# uc4h_esc_kiss_v100.net
KiCad netlist of a schematic drawn in EAGLE
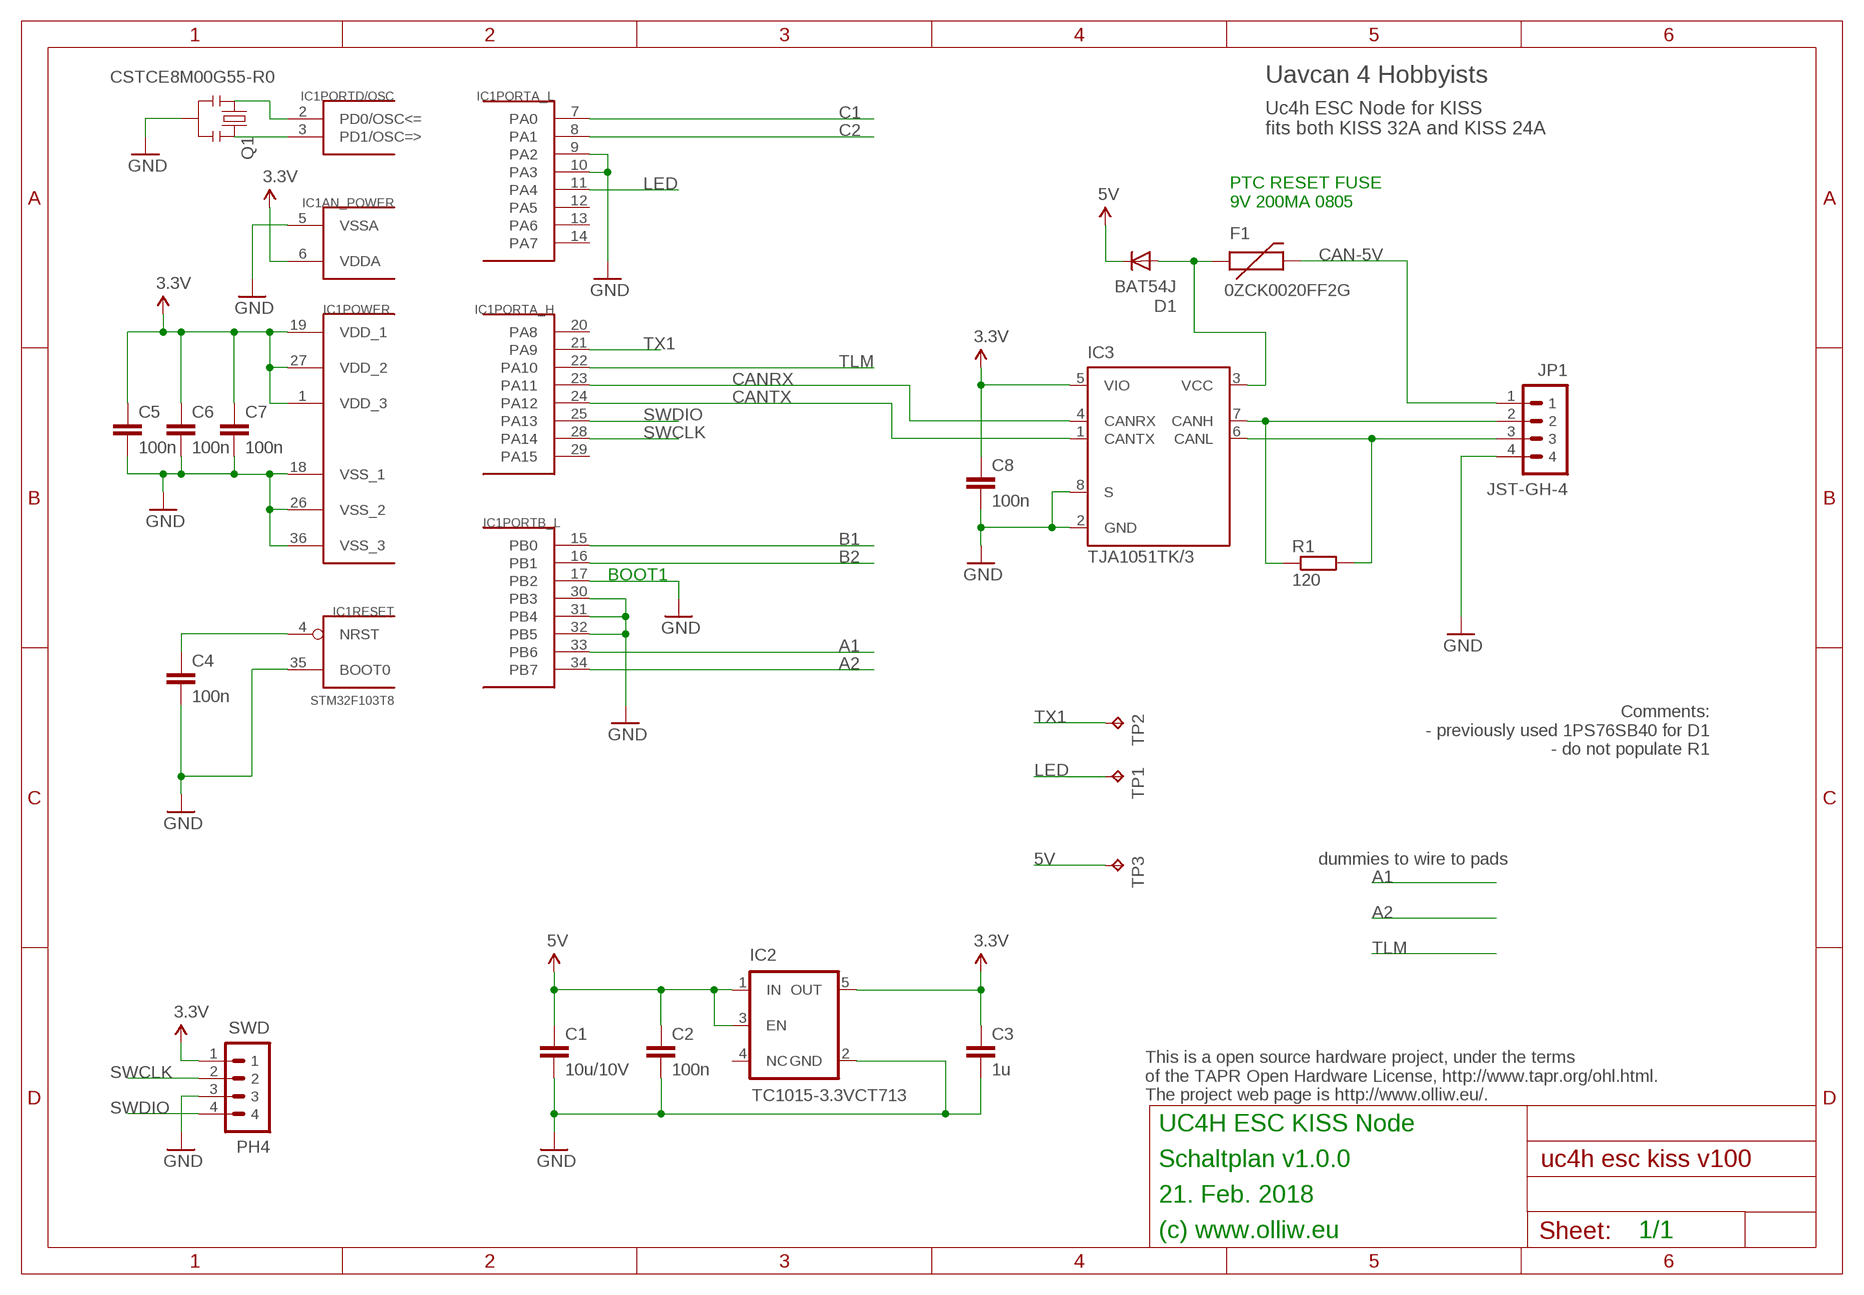
[diagram p0: schematic, sheet 1]

(export (version "E")
  (design (tool "Eeschema 10.0.6"))
  (components
    (comp (ref "C1")
      (value "10u/10V")
      (footprint "eagle-import:C1206")
      (libsource (lib "eagle-import") (part "C-EUC1206"))
    )
    (comp (ref "C2")
      (value "100n")
      (footprint "eagle-import:C0603K")
      (libsource (lib "eagle-import") (part "C-EUC0603K"))
    )
    (comp (ref "C3")
      (value "1u")
      (footprint "eagle-import:C0603K")
      (libsource (lib "eagle-import") (part "C-EUC0603K"))
    )
    (comp (ref "C4")
      (value "100n")
      (footprint "eagle-import:C0603K")
      (libsource (lib "eagle-import") (part "C-EUC0603K"))
    )
    (comp (ref "C5")
      (value "100n")
      (footprint "eagle-import:C0603K")
      (libsource (lib "eagle-import") (part "C-EUC0603K"))
    )
    (comp (ref "C6")
      (value "100n")
      (footprint "eagle-import:C0603K")
      (libsource (lib "eagle-import") (part "C-EUC0603K"))
    )
    (comp (ref "C7")
      (value "100n")
      (footprint "eagle-import:C0603K")
      (libsource (lib "eagle-import") (part "C-EUC0603K"))
    )
    (comp (ref "C8")
      (value "100n")
      (footprint "eagle-import:C0603K")
      (libsource (lib "eagle-import") (part "C-EUC0603K"))
    )
    (comp (ref "D1")
      (value "BAT54J")
      (footprint "eagle-import:SOD110-R")
      (libsource (lib "eagle-import") (part "DIODE-SOD110-R"))
    )
    (comp (ref "F1")
      (value "0ZCK0020FF2G")
      (footprint "eagle-import:FUSE-0805")
      (libsource (lib "eagle-import") (part "FUSE-PTCFUSE-0805"))
    )
    (comp (ref "IC1")
      (value "STM32F103T8")
      (footprint "eagle-import:VFQFPN36")
      (libsource (lib "eagle-import") (part "STM32F10XTXU6"))
    )
    (comp (ref "IC2")
      (value "TC1015-3.3VCT713")
      (footprint "eagle-import:SOT23-5")
      (libsource (lib "eagle-import") (part "V_REG_TPS76433SOT23-5"))
    )
    (comp (ref "IC3")
      (value "TJA1051TK/3")
      (footprint "eagle-import:HVSON8")
      (libsource (lib "eagle-import") (part "TJA1051TK/3"))
    )
    (comp (ref "JP1")
      (value "JST-GH-4")
      (footprint "eagle-import:SM04B-GHS-TB")
      (libsource (lib "eagle-import") (part "JST-GH-4"))
    )
    (comp (ref "Q1")
      (value "CSTCE8M00G55-R0")
      (footprint "eagle-import:RESONATOR-SMD")
      (libsource (lib "eagle-import") (part "RESONATORSMD"))
    )
    (comp (ref "R1")
      (value "120")
      (footprint "eagle-import:R0603")
      (libsource (lib "eagle-import") (part "R-EU_R0603"))
    )
    (comp (ref "SWD")
      (value "PH4")
      (footprint "eagle-import:4X1_1P27_OCT_BILEX")
      (libsource (lib "eagle-import") (part "P4X1_1P27-OCT_BILEX"))
    )
    (comp (ref "TP1")
      (value "TPB1,27")
      (footprint "eagle-import:B1,27")
      (libsource (lib "eagle-import") (part "TPB1,27"))
    )
    (comp (ref "TP2")
      (value "TPB1,27")
      (footprint "eagle-import:B1,27")
      (libsource (lib "eagle-import") (part "TPB1,27"))
    )
    (comp (ref "TP3")
      (value "TPB1,27")
      (footprint "eagle-import:B1,27")
      (libsource (lib "eagle-import") (part "TPB1,27"))
    )
  )
  (nets
    (net (code "1") (name "/A1") (class "Default")
      (node (ref "IC1") (pin "33") (pinfunction "PB6_33") (pintype "bidirectional"))
    )
    (net (code "2") (name "/A2") (class "Default")
      (node (ref "IC1") (pin "34") (pinfunction "PB7_34") (pintype "bidirectional"))
    )
    (net (code "3") (name "/B1") (class "Default")
      (node (ref "IC1") (pin "15") (pinfunction "PB0_15") (pintype "bidirectional"))
    )
    (net (code "4") (name "/B2") (class "Default")
      (node (ref "IC1") (pin "16") (pinfunction "PB1_16") (pintype "bidirectional"))
    )
    (net (code "5") (name "/C1") (class "Default")
      (node (ref "IC1") (pin "7") (pinfunction "PA0_7") (pintype "bidirectional"))
    )
    (net (code "6") (name "/C2") (class "Default")
      (node (ref "IC1") (pin "8") (pinfunction "PA1_8") (pintype "bidirectional"))
    )
    (net (code "7") (name "/CAN-5V") (class "Default")
      (node (ref "F1") (pin "2") (pinfunction "2_2") (pintype "bidirectional"))
      (node (ref "JP1") (pin "1") (pinfunction "1_1") (pintype "passive"))
    )
    (net (code "8") (name "/CANRX") (class "Default")
      (node (ref "IC1") (pin "23") (pinfunction "PA11_23") (pintype "bidirectional"))
      (node (ref "IC3") (pin "4") (pinfunction "CANRX_4") (pintype "output"))
    )
    (net (code "9") (name "/CANTX") (class "Default")
      (node (ref "IC1") (pin "24") (pinfunction "PA12_24") (pintype "bidirectional"))
      (node (ref "IC3") (pin "1") (pinfunction "CANTX_1") (pintype "input"))
    )
    (net (code "10") (name "/LED") (class "Default")
      (node (ref "IC1") (pin "11") (pinfunction "PA4_11") (pintype "bidirectional"))
      (node (ref "TP1") (pin "TP") (pinfunction "TP_TP") (pintype "input"))
    )
    (net (code "11") (name "/SWCLK") (class "Default")
      (node (ref "IC1") (pin "28") (pinfunction "PA14_28") (pintype "bidirectional"))
      (node (ref "SWD") (pin "2") (pinfunction "2_2") (pintype "passive"))
    )
    (net (code "12") (name "/SWDIO") (class "Default")
      (node (ref "IC1") (pin "25") (pinfunction "PA13_25") (pintype "bidirectional"))
      (node (ref "SWD") (pin "4") (pinfunction "4_4") (pintype "passive"))
    )
    (net (code "13") (name "/TLM") (class "Default")
      (node (ref "IC1") (pin "22") (pinfunction "PA10_22") (pintype "bidirectional"))
    )
    (net (code "14") (name "/TX1") (class "Default")
      (node (ref "IC1") (pin "21") (pinfunction "PA9_21") (pintype "bidirectional"))
      (node (ref "TP2") (pin "TP") (pinfunction "TP_TP") (pintype "input"))
    )
    (net (code "15") (name "3.3V") (class "Default")
      (node (ref "C3") (pin "1") (pinfunction "1_1") (pintype "passive"))
      (node (ref "C5") (pin "1") (pinfunction "1_1") (pintype "passive"))
      (node (ref "C6") (pin "1") (pinfunction "1_1") (pintype "passive"))
      (node (ref "C7") (pin "1") (pinfunction "1_1") (pintype "passive"))
      (node (ref "C8") (pin "1") (pinfunction "1_1") (pintype "passive"))
      (node (ref "IC1") (pin "1") (pinfunction "VDD_3_1") (pintype "power_in"))
      (node (ref "IC1") (pin "19") (pinfunction "VDD_1_19") (pintype "power_in"))
      (node (ref "IC1") (pin "27") (pinfunction "VDD_2_27") (pintype "power_in"))
      (node (ref "IC1") (pin "6") (pinfunction "VDDA_6") (pintype "power_in"))
      (node (ref "IC2") (pin "5") (pinfunction "OUT_5") (pintype "output"))
      (node (ref "IC3") (pin "5") (pinfunction "VIO_5") (pintype "power_in"))
      (node (ref "SWD") (pin "1") (pinfunction "1_1") (pintype "passive"))
    )
    (net (code "16") (name "5V") (class "Default")
      (node (ref "C1") (pin "1") (pinfunction "1_1") (pintype "passive"))
      (node (ref "C2") (pin "1") (pinfunction "1_1") (pintype "passive"))
      (node (ref "D1") (pin "C") (pinfunction "C_C") (pintype "passive"))
      (node (ref "IC2") (pin "1") (pinfunction "IN_1") (pintype "power_in"))
      (node (ref "IC2") (pin "3") (pinfunction "EN_3") (pintype "input"))
      (node (ref "TP3") (pin "TP") (pinfunction "TP_TP") (pintype "input"))
    )
    (net (code "17") (name "GND") (class "Default")
      (node (ref "C1") (pin "2") (pinfunction "2_2") (pintype "passive"))
      (node (ref "C2") (pin "2") (pinfunction "2_2") (pintype "passive"))
      (node (ref "C3") (pin "2") (pinfunction "2_2") (pintype "passive"))
      (node (ref "C4") (pin "2") (pinfunction "2_2") (pintype "passive"))
      (node (ref "C5") (pin "2") (pinfunction "2_2") (pintype "passive"))
      (node (ref "C6") (pin "2") (pinfunction "2_2") (pintype "passive"))
      (node (ref "C7") (pin "2") (pinfunction "2_2") (pintype "passive"))
      (node (ref "C8") (pin "2") (pinfunction "2_2") (pintype "passive"))
      (node (ref "IC1") (pin "10") (pinfunction "PA3_10") (pintype "bidirectional"))
      (node (ref "IC1") (pin "17") (pinfunction "PB2_17") (pintype "bidirectional"))
      (node (ref "IC1") (pin "18") (pinfunction "VSS_1_18") (pintype "power_in"))
      (node (ref "IC1") (pin "26") (pinfunction "VSS_2_26") (pintype "power_in"))
      (node (ref "IC1") (pin "30") (pinfunction "PB3_30") (pintype "bidirectional"))
      (node (ref "IC1") (pin "31") (pinfunction "PB4_31") (pintype "bidirectional"))
      (node (ref "IC1") (pin "32") (pinfunction "PB5_32") (pintype "bidirectional"))
      (node (ref "IC1") (pin "35") (pinfunction "BOOT0_35") (pintype "input"))
      (node (ref "IC1") (pin "36") (pinfunction "VSS_3_36") (pintype "power_in"))
      (node (ref "IC1") (pin "5") (pinfunction "VSSA_5") (pintype "power_in"))
      (node (ref "IC1") (pin "9") (pinfunction "PA2_9") (pintype "bidirectional"))
      (node (ref "IC2") (pin "2") (pinfunction "GND_2") (pintype "power_in"))
      (node (ref "IC3") (pin "2") (pinfunction "GND_2") (pintype "power_in"))
      (node (ref "IC3") (pin "8") (pinfunction "S_8") (pintype "input"))
      (node (ref "JP1") (pin "4") (pinfunction "4_4") (pintype "passive"))
      (node (ref "Q1") (pin "2") (pinfunction "2_2") (pintype "passive"))
      (node (ref "SWD") (pin "3") (pinfunction "3_3") (pintype "passive"))
    )
    (net (code "18") (name "Net-(IC1E-PD0{slash}OSC<=)") (class "Default")
      (node (ref "IC1") (pin "2") (pinfunction "PD0/OSC<=_2") (pintype "bidirectional"))
      (node (ref "Q1") (pin "1") (pinfunction "1_1") (pintype "passive"))
    )
    (net (code "19") (name "Net-(IC1E-PD1{slash}OSC=>)") (class "Default")
      (node (ref "IC1") (pin "3") (pinfunction "PD1/OSC=>_3") (pintype "bidirectional"))
      (node (ref "Q1") (pin "3") (pinfunction "3_3") (pintype "passive"))
    )
    (net (code "20") (name "Net-(IC1G-NRST)") (class "Default")
      (node (ref "C4") (pin "1") (pinfunction "1_1") (pintype "passive"))
      (node (ref "IC1") (pin "4") (pinfunction "NRST_4") (pintype "input"))
    )
    (net (code "21") (name "Net-(IC3-CANH)") (class "Default")
      (node (ref "IC3") (pin "7") (pinfunction "CANH_7") (pintype "bidirectional"))
      (node (ref "JP1") (pin "2") (pinfunction "2_2") (pintype "passive"))
      (node (ref "R1") (pin "1") (pinfunction "1_1") (pintype "passive"))
    )
    (net (code "22") (name "Net-(IC3-CANL)") (class "Default")
      (node (ref "IC3") (pin "6") (pinfunction "CANL_6") (pintype "bidirectional"))
      (node (ref "JP1") (pin "3") (pinfunction "3_3") (pintype "passive"))
      (node (ref "R1") (pin "2") (pinfunction "2_2") (pintype "passive"))
    )
    (net (code "23") (name "Net-(IC3-VCC)") (class "Default")
      (node (ref "D1") (pin "A") (pinfunction "A_A") (pintype "passive"))
      (node (ref "F1") (pin "1") (pinfunction "1_1") (pintype "bidirectional"))
      (node (ref "IC3") (pin "3") (pinfunction "VCC_3") (pintype "power_in"))
    )
    (net (code "24") (name "unconnected-(IC1B-PA8-Pad20)") (class "Default")
      (node (ref "IC1") (pin "20") (pinfunction "PA8_20") (pintype "bidirectional"))
    )
    (net (code "25") (name "unconnected-(IC1B-PA15-Pad29)") (class "Default")
      (node (ref "IC1") (pin "29") (pinfunction "PA15_29") (pintype "bidirectional"))
    )
    (net (code "26") (name "unconnected-(IC1C-PA5-Pad12)") (class "Default")
      (node (ref "IC1") (pin "12") (pinfunction "PA5_12") (pintype "bidirectional"))
    )
    (net (code "27") (name "unconnected-(IC1C-PA6-Pad13)") (class "Default")
      (node (ref "IC1") (pin "13") (pinfunction "PA6_13") (pintype "bidirectional"))
    )
    (net (code "28") (name "unconnected-(IC1C-PA7-Pad14)") (class "Default")
      (node (ref "IC1") (pin "14") (pinfunction "PA7_14") (pintype "bidirectional"))
    )
    (net (code "29") (name "unconnected-(IC2-NC-Pad4)") (class "Default")
      (node (ref "IC2") (pin "4") (pinfunction "NC_4") (pintype "passive"))
    )
  )
)
